# I2C.net
KiCad netlist of a schematic drawn in Altium Designer
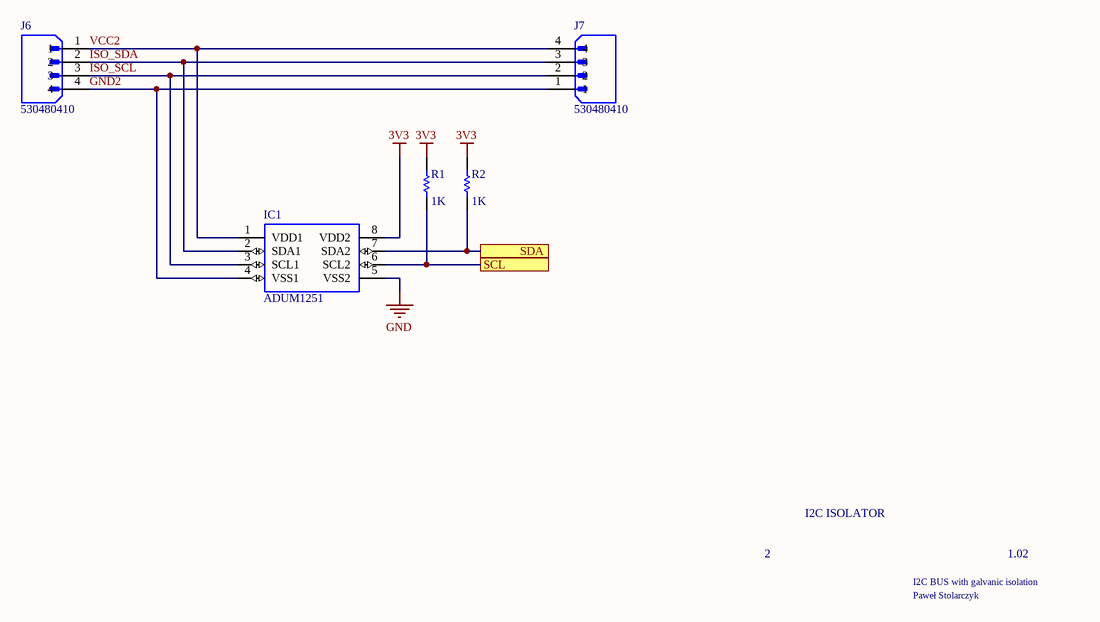
[diagram p0: I2C.SchDoc]

(export (version "E")
  (design (tool "Eeschema 10.0.6"))
  (components
    (comp (ref "IC1")
      (value "ADUM1251")
      (footprint "SOIC127P600X175-8N")
      (description "IÂ²C Digital Isolator 2500Vrms 2 Channel 1Mbps 25kV/Âµs CMTI 8-SOIC (0.154, 3.90mm Width)")
      (fields (field (name "MF") "Analog Devices"))
      (libsource (lib "ADUM1251") (part "ADUM1251"))
    )
    (comp (ref "J6")
      (value "530480410")
      (footprint "MOLEX_530480410")
      (libsource (lib "") (part "530480410_1"))
    )
    (comp (ref "J7")
      (value "530480410")
      (footprint "MOLEX_530480410")
      (libsource (lib "530480410") (part "530480410"))
    )
    (comp (ref "R1")
      (value "1K")
      (footprint "0402")
      (description "Resistor")
      (fields (field (name "Comment") "Res1") (field (name "PUBLISHER") "Altium Limited"))
      (libsource (lib "Miscellaneous Devices") (part "Res1"))
    )
    (comp (ref "R2")
      (value "1K")
      (footprint "0402")
      (description "Resistor")
      (fields (field (name "Comment") "Res1") (field (name "PUBLISHER") "Altium Limited"))
      (libsource (lib "Miscellaneous Devices") (part "Res1"))
    )
  )
  (nets
    (net (code "1") (name "/GND2") (class "Default")
      (node (ref "IC1") (pin "4") (pinfunction "VSS1_4") (pintype "bidirectional"))
      (node (ref "J6") (pin "4") (pinfunction "4_4") (pintype "passive"))
      (node (ref "J7") (pin "1") (pinfunction "1_1") (pintype "passive"))
    )
    (net (code "2") (name "/ISO_SCL") (class "Default")
      (node (ref "IC1") (pin "3") (pinfunction "SCL1_3") (pintype "bidirectional"))
      (node (ref "J6") (pin "3") (pinfunction "3_3") (pintype "passive"))
      (node (ref "J7") (pin "2") (pinfunction "2_2") (pintype "passive"))
    )
    (net (code "3") (name "/ISO_SDA") (class "Default")
      (node (ref "IC1") (pin "2") (pinfunction "SDA1_2") (pintype "bidirectional"))
      (node (ref "J6") (pin "2") (pinfunction "2_2") (pintype "passive"))
      (node (ref "J7") (pin "3") (pinfunction "3_3") (pintype "passive"))
    )
    (net (code "4") (name "/SCL") (class "Default")
      (node (ref "IC1") (pin "6") (pinfunction "SCL2_6") (pintype "bidirectional"))
      (node (ref "R1") (pin "1") (pinfunction "1_1") (pintype "passive"))
    )
    (net (code "5") (name "/SDA") (class "Default")
      (node (ref "IC1") (pin "7") (pinfunction "SDA2_7") (pintype "bidirectional"))
      (node (ref "R2") (pin "1") (pinfunction "1_1") (pintype "passive"))
    )
    (net (code "6") (name "/VCC2") (class "Default")
      (node (ref "IC1") (pin "1") (pinfunction "VDD1_1") (pintype "power_in"))
      (node (ref "J6") (pin "1") (pinfunction "1_1") (pintype "passive"))
      (node (ref "J7") (pin "4") (pinfunction "4_4") (pintype "passive"))
    )
    (net (code "7") (name "3V3") (class "Default")
      (node (ref "IC1") (pin "8") (pinfunction "VDD2_8") (pintype "power_in"))
      (node (ref "R1") (pin "2") (pinfunction "2_2") (pintype "passive"))
      (node (ref "R2") (pin "2") (pinfunction "2_2") (pintype "passive"))
    )
    (net (code "8") (name "GND") (class "Default")
      (node (ref "IC1") (pin "5") (pinfunction "VSS2_5") (pintype "power_in"))
    )
  )
)
